# Power_managment.net
KiCad netlist of a schematic drawn in Altium Designer
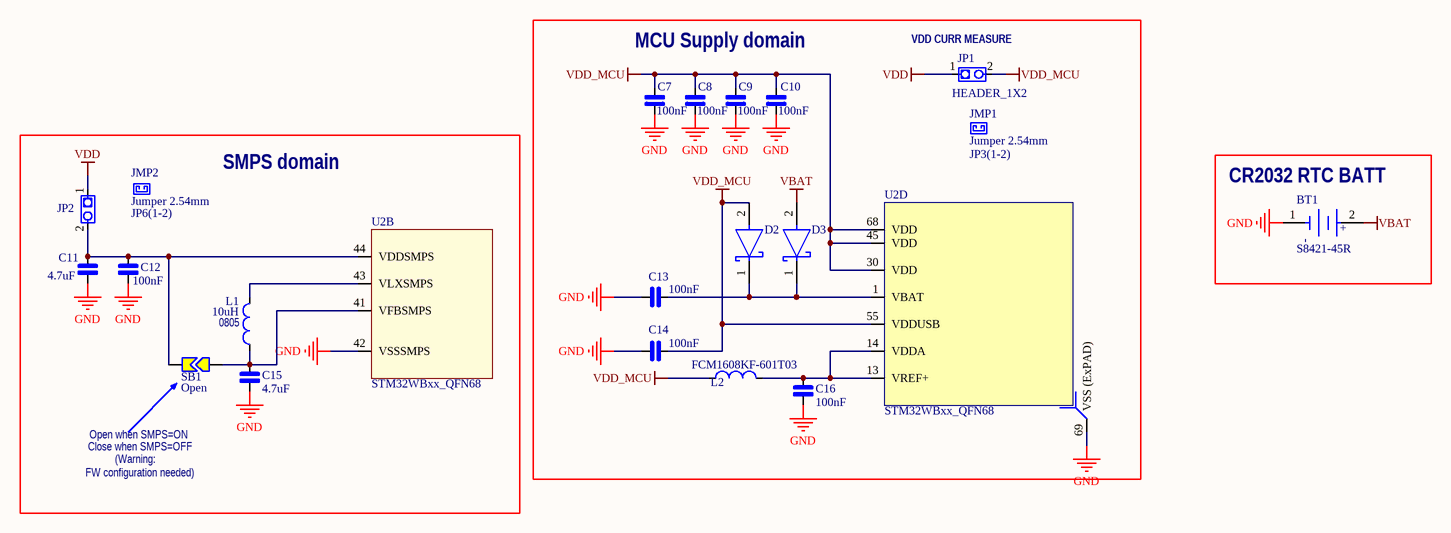
[diagram p0: Power_managment.SchDoc]

(export (version "E")
  (design (tool "Eeschema 10.0.6"))
  (components
    (comp (ref "BT1")
      (value "S8421-45R")
      (footprint "FP-S8421-45R-MFG")
      (description "BATTERY HOLDER COIN 20MM SMD")
      (libsource (lib "Altium Content Vault") (part "60d3b5b901a8747834971d0eb8cf3fd"))
    )
    (comp (ref "C7")
      (value "100nF")
      (footprint "C1206")
      (description "Capacitor_not polarized")
      (libsource (lib "ST_Lib3D") (part "CAP_NPOL"))
    )
    (comp (ref "C8")
      (value "100nF")
      (footprint "C1206")
      (description "Capacitor_not polarized")
      (libsource (lib "ST_Lib3D") (part "CAP_NPOL"))
    )
    (comp (ref "C9")
      (value "100nF")
      (footprint "C1206")
      (description "Capacitor_not polarized")
      (libsource (lib "ST_Lib3D") (part "CAP_NPOL"))
    )
    (comp (ref "C10")
      (value "100nF")
      (footprint "C1206")
      (description "Capacitor_not polarized")
      (libsource (lib "ST_Lib3D") (part "CAP_NPOL"))
    )
    (comp (ref "C11")
      (value "4.7uF")
      (footprint "C1206")
      (description "Capacitor_not polarized")
      (libsource (lib "ST_Lib3D") (part "CAP_NPOL"))
    )
    (comp (ref "C12")
      (value "100nF")
      (footprint "C1206")
      (description "Capacitor_not polarized")
      (libsource (lib "ST_Lib3D") (part "CAP_NPOL"))
    )
    (comp (ref "C13")
      (value "100nF")
      (footprint "C1206")
      (description "Capacitor_not polarized")
      (libsource (lib "ST_Lib3D") (part "CAP_NPOL"))
    )
    (comp (ref "C14")
      (value "100nF")
      (footprint "C1206")
      (description "Capacitor_not polarized")
      (libsource (lib "ST_Lib3D") (part "CAP_NPOL"))
    )
    (comp (ref "C15")
      (value "4.7uF")
      (footprint "C1206")
      (description "Capacitor_not polarized")
      (libsource (lib "ST_Lib3D") (part "CAP_NPOL"))
    )
    (comp (ref "C16")
      (value "100nF")
      (footprint "C1206")
      (description "Capacitor_not polarized")
      (libsource (lib "ST_Lib3D") (part "CAP_NPOL"))
    )
    (comp (ref "D2")
      (value "LS4148-GS18")
      (footprint "FP-6_560-5006_01-4-MFG")
      (description "DIODE GEN PURP 75V 150MA SOD80")
      (fields
        (field (name "MANUFACTURER") "Vishay")
        (field (name "OCTOPART") "https://octopart.com/ls4148-gs18-vishay-55507867")
      )
      (libsource (lib "Altium Content Vault") (part "1d6ec82d83fb6aee721767c19dac4b9"))
    )
    (comp (ref "D3")
      (value "LS4148-GS18")
      (footprint "FP-6_560-5006_01-4-MFG")
      (description "DIODE GEN PURP 75V 150MA SOD80")
      (fields
        (field (name "MANUFACTURER") "Vishay")
        (field (name "OCTOPART") "https://octopart.com/ls4148-gs18-vishay-55507867")
      )
      (libsource (lib "Altium Content Vault") (part "1d6ec82d83fb6aee721767c19dac4b9"))
    )
    (comp (ref "JMP1")
      (value "Jumper 2.54mm")
      (footprint "Jumper 2.54mm BLACK")
      (fields (field (name "DEFAULT") "JP3(1-2)"))
      (libsource (lib "Connector") (part "Jumper 2.54mm"))
    )
    (comp (ref "JMP2")
      (value "Jumper 2.54mm")
      (footprint "Jumper 2.54mm BLACK")
      (fields (field (name "DEFAULT") "JP6(1-2)"))
      (libsource (lib "Connector") (part "Jumper 2.54mm"))
    )
    (comp (ref "JP1")
      (value "HEADER_1X2")
      (footprint "Header M 1x2x2.54 TH V")
      (libsource (lib "Connector") (part "HEADER_1X2_L"))
    )
    (comp (ref "JP2")
      (value "HEADER_1X2")
      (footprint "GP_2x1_2mm")
      (libsource (lib "Connector") (part "HEADER_1X2_L"))
    )
    (comp (ref "L1")
      (value "10uH")
      (footprint "0805_COIL")
      (description "Coil Wurtz 10uH ref: 74479777310A")
      (libsource (lib "Passive") (part "IND_74479777310A"))
    )
    (comp (ref "L2")
      (value "FCM1608KF-601T03")
      (footprint "0603_COIL")
      (libsource (lib "Passive") (part "IND_FCM1608KF-601T03"))
    )
    (comp (ref "SB1")
      (value "Open")
      (footprint "SB-tiny")
      (description "Solder Jumper")
      (fields (field (name "PUBLISHER") "Altium Limited"))
      (libsource (lib "Passive") (part "Strap2"))
    )
    (comp (ref "U2")
      (value "STM32WBxx_QFN68")
      (footprint "VFQFPN68_8x8x0.1_p0.4")
      (libsource (lib "Active") (part "STM32WBxx_QFN68"))
    )
  )
  (nets
    (net (code "1") (name "GND") (class "Default")
      (node (ref "BT1") (pin "1") (pinfunction "C_1") (pintype "passive"))
      (node (ref "C10") (pin "2") (pinfunction "2_2") (pintype "passive"))
      (node (ref "C11") (pin "2") (pinfunction "2_2") (pintype "passive"))
      (node (ref "C12") (pin "2") (pinfunction "2_2") (pintype "passive"))
      (node (ref "C13") (pin "2") (pinfunction "2_2") (pintype "passive"))
      (node (ref "C14") (pin "2") (pinfunction "2_2") (pintype "passive"))
      (node (ref "C15") (pin "2") (pinfunction "2_2") (pintype "passive"))
      (node (ref "C16") (pin "2") (pinfunction "2_2") (pintype "passive"))
      (node (ref "C7") (pin "2") (pinfunction "2_2") (pintype "passive"))
      (node (ref "C8") (pin "2") (pinfunction "2_2") (pintype "passive"))
      (node (ref "C9") (pin "2") (pinfunction "2_2") (pintype "passive"))
      (node (ref "U2") (pin "42") (pinfunction "VSSSMPS_42") (pintype "passive"))
      (node (ref "U2") (pin "69") (pinfunction "VSS_(ExPAD)_69") (pintype "passive"))
    )
    (net (code "2") (name "Net-(D2-C)") (class "Default")
      (node (ref "C13") (pin "1") (pinfunction "1_1") (pintype "passive"))
      (node (ref "D2") (pin "1") (pinfunction "C_1") (pintype "passive"))
      (node (ref "D3") (pin "1") (pinfunction "C_1") (pintype "passive"))
      (node (ref "U2") (pin "1") (pinfunction "VBAT_1") (pintype "passive"))
    )
    (net (code "3") (name "Net-(U2B-VDDSMPS)") (class "Default")
      (node (ref "C11") (pin "1") (pinfunction "1_1") (pintype "passive"))
      (node (ref "C12") (pin "1") (pinfunction "1_1") (pintype "passive"))
      (node (ref "JP2") (pin "2") (pinfunction "2_2") (pintype "passive"))
      (node (ref "SB1") (pin "2") (pinfunction "2_2") (pintype "passive"))
      (node (ref "U2") (pin "44") (pinfunction "VDDSMPS_44") (pintype "passive"))
    )
    (net (code "4") (name "Net-(U2B-VFBSMPS)") (class "Default")
      (node (ref "C15") (pin "1") (pinfunction "1_1") (pintype "passive"))
      (node (ref "L1") (pin "1") (pinfunction "1_1") (pintype "passive"))
      (node (ref "SB1") (pin "1") (pinfunction "1_1") (pintype "passive"))
      (node (ref "U2") (pin "41") (pinfunction "VFBSMPS_41") (pintype "passive"))
    )
    (net (code "5") (name "Net-(U2B-VLXSMPS)") (class "Default")
      (node (ref "L1") (pin "2") (pinfunction "2_2") (pintype "passive"))
      (node (ref "U2") (pin "43") (pinfunction "VLXSMPS_43") (pintype "passive"))
    )
    (net (code "6") (name "Net-(U2D-VDDA)") (class "Default")
      (node (ref "C16") (pin "1") (pinfunction "1_1") (pintype "passive"))
      (node (ref "L2") (pin "2") (pinfunction "2_2") (pintype "passive"))
      (node (ref "U2") (pin "13") (pinfunction "VREF+_13") (pintype "passive"))
      (node (ref "U2") (pin "14") (pinfunction "VDDA_14") (pintype "passive"))
    )
    (net (code "7") (name "VBAT") (class "Default")
      (node (ref "BT1") (pin "2") (pinfunction "A_2") (pintype "passive"))
      (node (ref "D3") (pin "2") (pinfunction "A_2") (pintype "passive"))
    )
    (net (code "8") (name "VDD") (class "Default")
      (node (ref "JP1") (pin "1") (pinfunction "1_1") (pintype "passive"))
      (node (ref "JP2") (pin "1") (pinfunction "1_1") (pintype "passive"))
    )
    (net (code "9") (name "VDD_MCU") (class "Default")
      (node (ref "C10") (pin "1") (pinfunction "1_1") (pintype "passive"))
      (node (ref "C14") (pin "1") (pinfunction "1_1") (pintype "passive"))
      (node (ref "C7") (pin "1") (pinfunction "1_1") (pintype "passive"))
      (node (ref "C8") (pin "1") (pinfunction "1_1") (pintype "passive"))
      (node (ref "C9") (pin "1") (pinfunction "1_1") (pintype "passive"))
      (node (ref "D2") (pin "2") (pinfunction "A_2") (pintype "passive"))
      (node (ref "JP1") (pin "2") (pinfunction "2_2") (pintype "passive"))
      (node (ref "L2") (pin "1") (pinfunction "1_1") (pintype "passive"))
      (node (ref "U2") (pin "30") (pinfunction "VDD_30") (pintype "passive"))
      (node (ref "U2") (pin "45") (pinfunction "VDD_45") (pintype "passive"))
      (node (ref "U2") (pin "55") (pinfunction "VDDUSB_55") (pintype "passive"))
      (node (ref "U2") (pin "68") (pinfunction "VDD_68") (pintype "passive"))
    )
  )
)
